# Center_Dash.net
KiCad netlist of a schematic drawn in EAGLE
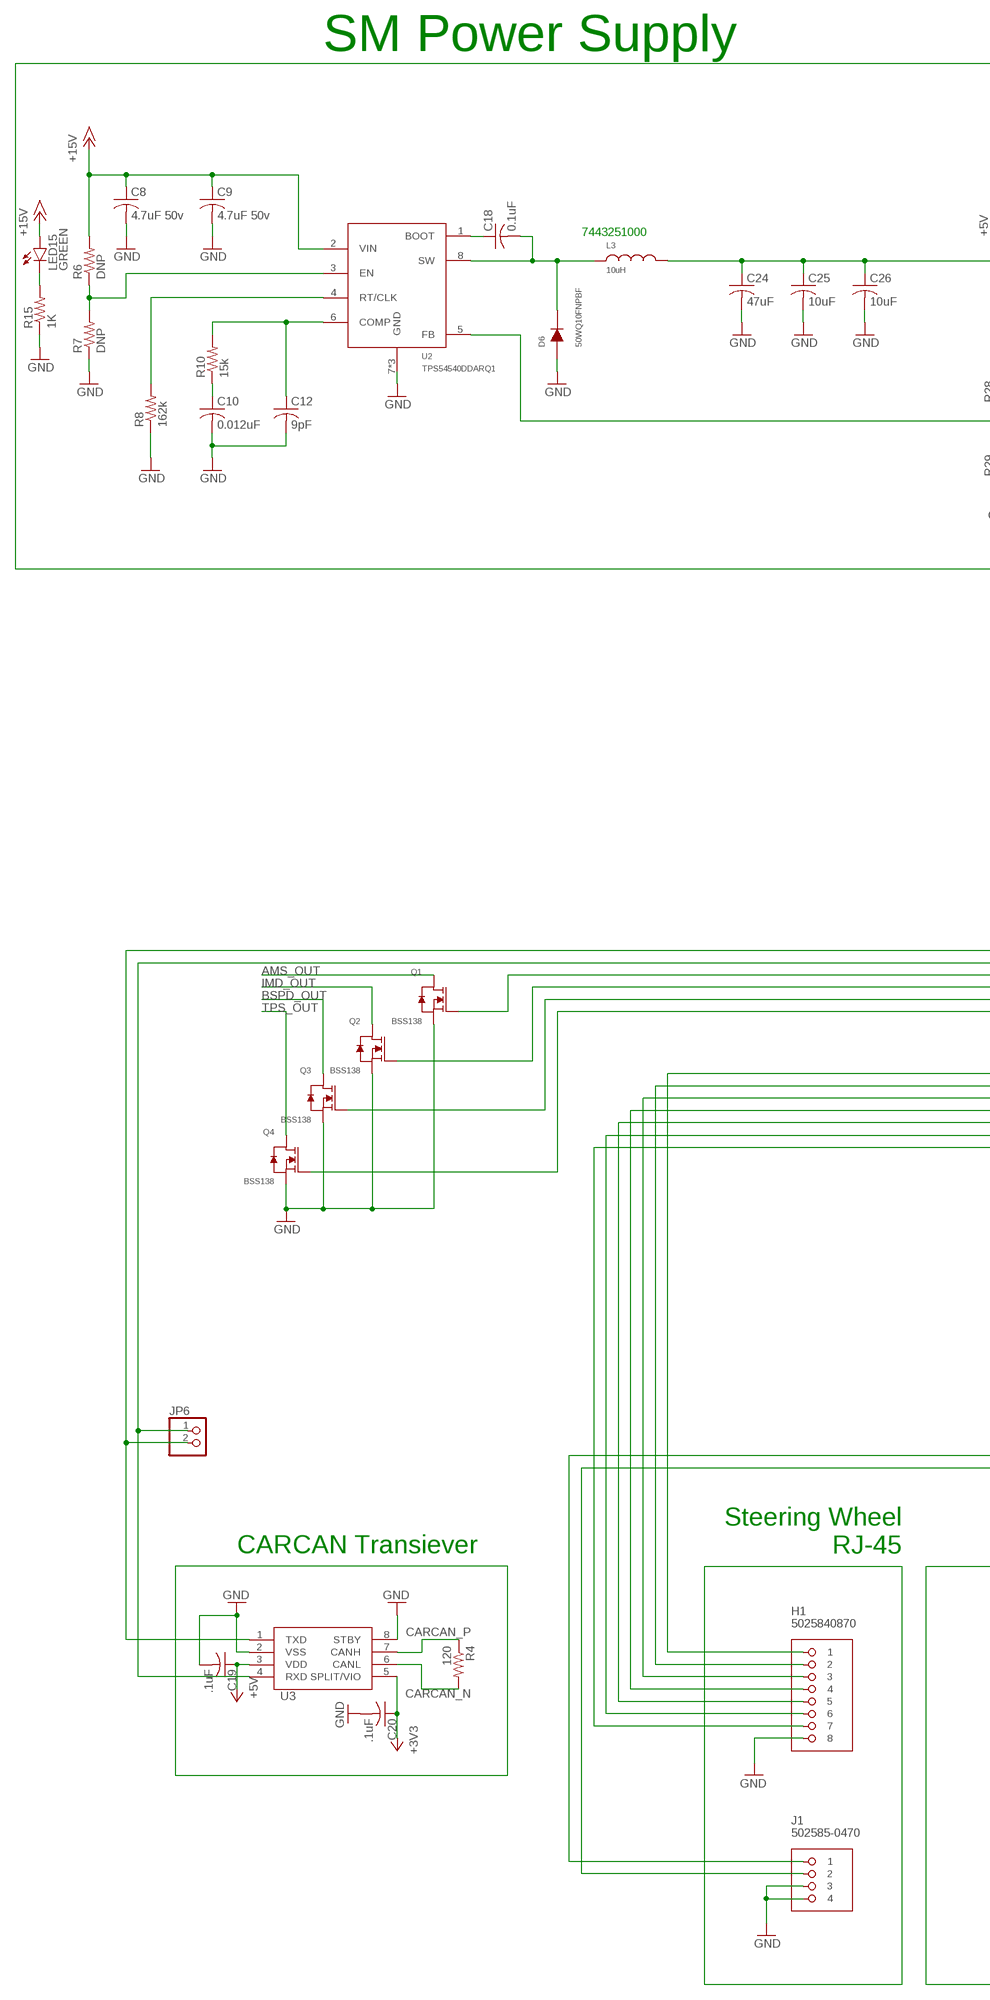
[diagram p0: schematic, sheet 1, part 1 of 2]
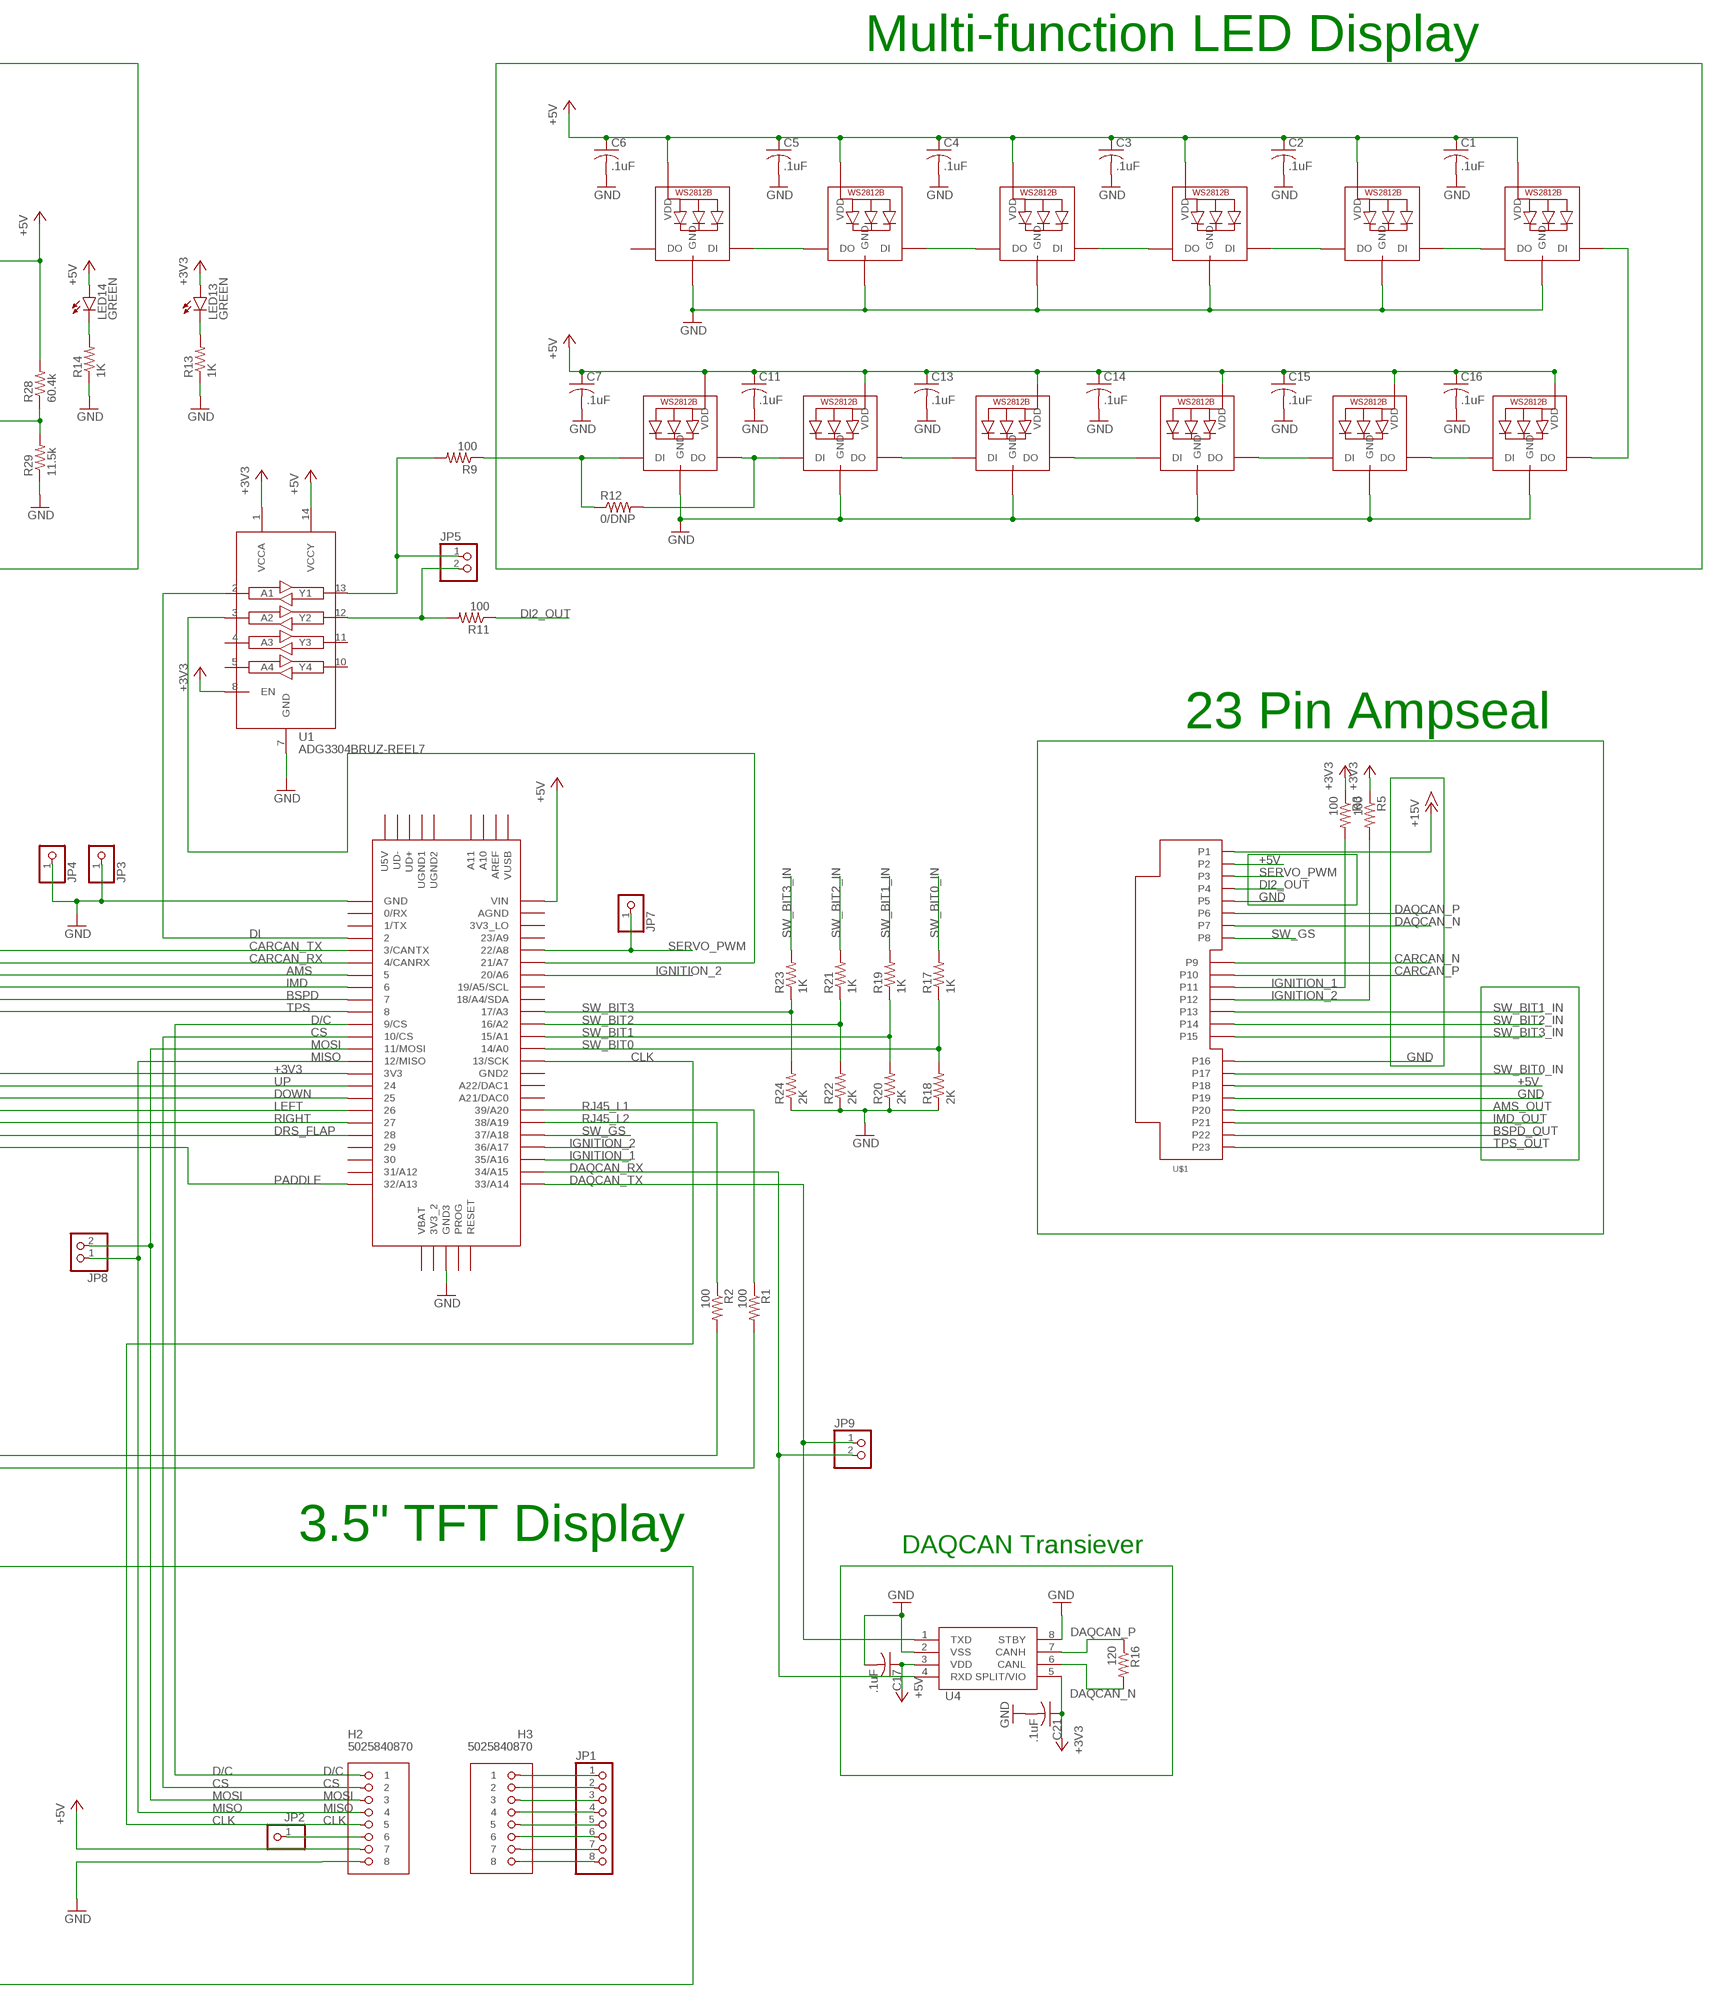
[diagram p1: schematic, sheet 1, part 2 of 2]

(export (version "E")
  (design (tool "Eeschema 10.0.6"))
  (components
    (comp (ref "C1")
      (value ".1uF")
      (footprint "eagle-import:C0603K")
      (fields (field (name "PARTNO") "GRM188R61A106KE69D"))
      (libsource (lib "eagle-import") (part "C-USC0603K"))
    )
    (comp (ref "C2")
      (value ".1uF")
      (footprint "eagle-import:C0603K")
      (fields (field (name "PARTNO") "GRM188R61A106KE69D"))
      (libsource (lib "eagle-import") (part "C-USC0603K"))
    )
    (comp (ref "C3")
      (value ".1uF")
      (footprint "eagle-import:C0603K")
      (fields (field (name "PARTNO") "GRM188R61A106KE69D"))
      (libsource (lib "eagle-import") (part "C-USC0603K"))
    )
    (comp (ref "C4")
      (value ".1uF")
      (footprint "eagle-import:C0603K")
      (fields (field (name "PARTNO") "GRM188R61A106KE69D"))
      (libsource (lib "eagle-import") (part "C-USC0603K"))
    )
    (comp (ref "C5")
      (value ".1uF")
      (footprint "eagle-import:C0603K")
      (fields (field (name "PARTNO") "GRM188R61A106KE69D"))
      (libsource (lib "eagle-import") (part "C-USC0603K"))
    )
    (comp (ref "C6")
      (value ".1uF")
      (footprint "eagle-import:C0603K")
      (fields (field (name "PARTNO") "GRM188R61A106KE69D"))
      (libsource (lib "eagle-import") (part "C-USC0603K"))
    )
    (comp (ref "C7")
      (value ".1uF")
      (footprint "eagle-import:C0603K")
      (fields (field (name "PARTNO") "GRM188R61A106KE69D"))
      (libsource (lib "eagle-import") (part "C-USC0603K"))
    )
    (comp (ref "C8")
      (value "4.7uF 50v")
      (footprint "eagle-import:C1206")
      (fields (field (name "PARTNO") "GRM31CR71H475KA12L"))
      (libsource (lib "eagle-import") (part "C-USC1206"))
    )
    (comp (ref "C9")
      (value "4.7uF 50v")
      (footprint "eagle-import:C1206")
      (fields (field (name "PARTNO") "GRM31CR71H475KA12L"))
      (libsource (lib "eagle-import") (part "C-USC1206"))
    )
    (comp (ref "C10")
      (value "0.012uF")
      (footprint "eagle-import:C0603K")
      (fields (field (name "PARTNO") "GRM188R71H123KA01D"))
      (libsource (lib "eagle-import") (part "C-USC0603K"))
    )
    (comp (ref "C11")
      (value ".1uF")
      (footprint "eagle-import:C0603K")
      (fields (field (name "PARTNO") "GRM188R61A106KE69D"))
      (libsource (lib "eagle-import") (part "C-USC0603K"))
    )
    (comp (ref "C12")
      (value "9pF")
      (footprint "eagle-import:C0603K")
      (fields (field (name "PARTNO") "GRM1885C1H9R0DA01D"))
      (libsource (lib "eagle-import") (part "C-USC0603K"))
    )
    (comp (ref "C13")
      (value ".1uF")
      (footprint "eagle-import:C0603K")
      (fields (field (name "PARTNO") "GRM188R61A106KE69D"))
      (libsource (lib "eagle-import") (part "C-USC0603K"))
    )
    (comp (ref "C14")
      (value ".1uF")
      (footprint "eagle-import:C0603K")
      (fields (field (name "PARTNO") "GRM188R61A106KE69D"))
      (libsource (lib "eagle-import") (part "C-USC0603K"))
    )
    (comp (ref "C15")
      (value ".1uF")
      (footprint "eagle-import:C0603K")
      (fields (field (name "PARTNO") "GRM188R61A106KE69D"))
      (libsource (lib "eagle-import") (part "C-USC0603K"))
    )
    (comp (ref "C16")
      (value ".1uF")
      (footprint "eagle-import:C0603K")
      (fields (field (name "PARTNO") "GRM188R61A106KE69D"))
      (libsource (lib "eagle-import") (part "C-USC0603K"))
    )
    (comp (ref "C17")
      (value ".1uF")
      (footprint "eagle-import:C0805")
      (libsource (lib "eagle-import") (part "C-USC0805"))
    )
    (comp (ref "C18")
      (value "0.1uF")
      (footprint "eagle-import:C0603K")
      (fields (field (name "PARTNO") "GRM188R71E104KA01D"))
      (libsource (lib "eagle-import") (part "C-USC0603K"))
    )
    (comp (ref "C19")
      (value ".1uF")
      (footprint "eagle-import:C0805")
      (libsource (lib "eagle-import") (part "C-USC0805"))
    )
    (comp (ref "C20")
      (value ".1uF")
      (footprint "eagle-import:C0805")
      (libsource (lib "eagle-import") (part "C-USC0805"))
    )
    (comp (ref "C21")
      (value ".1uF")
      (footprint "eagle-import:C0805")
      (libsource (lib "eagle-import") (part "C-USC0805"))
    )
    (comp (ref "C24")
      (value "47uF")
      (footprint "eagle-import:C1206")
      (fields (field (name "PARTNO") "GRM31CR61A476ME15L"))
      (libsource (lib "eagle-import") (part "C-USC1206"))
    )
    (comp (ref "C25")
      (value "10uF")
      (footprint "eagle-import:C0603K")
      (fields (field (name "PARTNO") "GRM188R61A106KE69D"))
      (libsource (lib "eagle-import") (part "C-USC0603K"))
    )
    (comp (ref "C26")
      (value "10uF")
      (footprint "eagle-import:C0603K")
      (fields (field (name "PARTNO") "GRM188R61A106KE69D"))
      (libsource (lib "eagle-import") (part "C-USC0603K"))
    )
    (comp (ref "D6")
      (value "50WQ10FNPBF")
      (footprint "eagle-import:DPAK")
      (fields (field (name "PARTNO") "VS-50WQ10FNPBF"))
      (libsource (lib "eagle-import") (part "VISHAY-50WQ10FNPBF"))
    )
    (comp (ref "H1")
      (value "5025840870")
      (footprint "eagle-import:MOLEX-CLIKMATE-8-VERTICAL-HEADER")
      (libsource (lib "eagle-import") (part "MOLEX_CLICKMATE-8-VERTICAL"))
    )
    (comp (ref "H2")
      (value "5025840870")
      (footprint "eagle-import:MOLEX-CLIKMATE-8-VERTICAL-HEADER")
      (libsource (lib "eagle-import") (part "MOLEX_CLICKMATE-8-VERTICAL"))
    )
    (comp (ref "H3")
      (value "5025840870")
      (footprint "eagle-import:MOLEX-CLIKMATE-8-VERTICAL-HEADER")
      (libsource (lib "eagle-import") (part "MOLEX_CLICKMATE-8-VERTICAL"))
    )
    (comp (ref "J1")
      (value "502585-0470")
      (footprint "eagle-import:MOLEX-CLIKMATE-4-R_A")
      (libsource (lib "eagle-import") (part "MOLEX_CLICKMATE-4-R/A"))
    )
    (comp (ref "JP1")
      (value "PINHD-1X8")
      (footprint "eagle-import:1X08")
      (libsource (lib "eagle-import") (part "PINHD-1X8"))
    )
    (comp (ref "JP2")
      (value "PINHD-1X1")
      (footprint "eagle-import:1X01")
      (libsource (lib "eagle-import") (part "PINHD-1X1"))
    )
    (comp (ref "JP3")
      (value "PINHD-1X1")
      (footprint "eagle-import:1X01")
      (libsource (lib "eagle-import") (part "PINHD-1X1"))
    )
    (comp (ref "JP4")
      (value "PINHD-1X1")
      (footprint "eagle-import:1X01")
      (libsource (lib "eagle-import") (part "PINHD-1X1"))
    )
    (comp (ref "JP5")
      (value "PINHD-1X2")
      (footprint "eagle-import:1X02")
      (libsource (lib "eagle-import") (part "PINHD-1X2"))
    )
    (comp (ref "JP6")
      (value "PINHD-1X2")
      (footprint "eagle-import:1X02")
      (libsource (lib "eagle-import") (part "PINHD-1X2"))
    )
    (comp (ref "JP7")
      (value "PINHD-1X1")
      (footprint "eagle-import:1X01")
      (libsource (lib "eagle-import") (part "PINHD-1X1"))
    )
    (comp (ref "JP8")
      (value "PINHD-1X2")
      (footprint "eagle-import:1X02")
      (libsource (lib "eagle-import") (part "PINHD-1X2"))
    )
    (comp (ref "JP9")
      (value "PINHD-1X2")
      (footprint "eagle-import:1X02")
      (libsource (lib "eagle-import") (part "PINHD-1X2"))
    )
    (comp (ref "L3")
      (value "10uH")
      (footprint "eagle-import:WURTH-744325XXXX")
      (fields (field (name "PARTNO") "7443251000"))
      (libsource (lib "eagle-import") (part "WURTH-744325XXXX"))
    )
    (comp (ref "LED1")
      (value "WS2812B5050")
      (footprint "eagle-import:WS2812B")
      (libsource (lib "eagle-import") (part "WS2812B5050"))
    )
    (comp (ref "LED2")
      (value "WS2812B5050")
      (footprint "eagle-import:WS2812B")
      (libsource (lib "eagle-import") (part "WS2812B5050"))
    )
    (comp (ref "LED3")
      (value "WS2812B5050")
      (footprint "eagle-import:WS2812B")
      (libsource (lib "eagle-import") (part "WS2812B5050"))
    )
    (comp (ref "LED4")
      (value "WS2812B5050")
      (footprint "eagle-import:WS2812B")
      (libsource (lib "eagle-import") (part "WS2812B5050"))
    )
    (comp (ref "LED5")
      (value "WS2812B5050")
      (footprint "eagle-import:WS2812B")
      (libsource (lib "eagle-import") (part "WS2812B5050"))
    )
    (comp (ref "LED6")
      (value "WS2812B5050")
      (footprint "eagle-import:WS2812B")
      (libsource (lib "eagle-import") (part "WS2812B5050"))
    )
    (comp (ref "LED7")
      (value "WS2812B5050")
      (footprint "eagle-import:WS2812B")
      (libsource (lib "eagle-import") (part "WS2812B5050"))
    )
    (comp (ref "LED8")
      (value "WS2812B5050")
      (footprint "eagle-import:WS2812B")
      (libsource (lib "eagle-import") (part "WS2812B5050"))
    )
    (comp (ref "LED9")
      (value "WS2812B5050")
      (footprint "eagle-import:WS2812B")
      (libsource (lib "eagle-import") (part "WS2812B5050"))
    )
    (comp (ref "LED10")
      (value "WS2812B5050")
      (footprint "eagle-import:WS2812B")
      (libsource (lib "eagle-import") (part "WS2812B5050"))
    )
    (comp (ref "LED11")
      (value "WS2812B5050")
      (footprint "eagle-import:WS2812B")
      (libsource (lib "eagle-import") (part "WS2812B5050"))
    )
    (comp (ref "LED12")
      (value "WS2812B5050")
      (footprint "eagle-import:WS2812B")
      (libsource (lib "eagle-import") (part "WS2812B5050"))
    )
    (comp (ref "LED13")
      (value "GREEN")
      (footprint "eagle-import:CHIP-LED0805")
      (fields (field (name "PARTNO") "598-8170-107F"))
      (libsource (lib "eagle-import") (part "LEDCHIP-LED0805"))
    )
    (comp (ref "LED14")
      (value "GREEN")
      (footprint "eagle-import:CHIP-LED0805")
      (fields (field (name "PARTNO") "598-8170-107F"))
      (libsource (lib "eagle-import") (part "LEDCHIP-LED0805"))
    )
    (comp (ref "LED15")
      (value "GREEN")
      (footprint "eagle-import:CHIP-LED0805")
      (fields (field (name "PARTNO") "598-8170-107F"))
      (libsource (lib "eagle-import") (part "LEDCHIP-LED0805"))
    )
    (comp (ref "Q1")
      (value "BSS138")
      (footprint "eagle-import:BSS138")
      (libsource (lib "eagle-import") (part "BSS138"))
    )
    (comp (ref "Q2")
      (value "BSS138")
      (footprint "eagle-import:BSS138")
      (libsource (lib "eagle-import") (part "BSS138"))
    )
    (comp (ref "Q3")
      (value "BSS138")
      (footprint "eagle-import:BSS138")
      (libsource (lib "eagle-import") (part "BSS138"))
    )
    (comp (ref "Q4")
      (value "BSS138")
      (footprint "eagle-import:BSS138")
      (libsource (lib "eagle-import") (part "BSS138"))
    )
    (comp (ref "R1")
      (value "100")
      (footprint "eagle-import:R0805")
      (libsource (lib "eagle-import") (part "rcl_R-US_R0805"))
    )
    (comp (ref "R2")
      (value "100")
      (footprint "eagle-import:R0805")
      (libsource (lib "eagle-import") (part "rcl_R-US_R0805"))
    )
    (comp (ref "R3")
      (value "100")
      (footprint "eagle-import:R0805")
      (libsource (lib "eagle-import") (part "rcl_R-US_R0805"))
    )
    (comp (ref "R4")
      (value "120")
      (footprint "eagle-import:R0805")
      (libsource (lib "eagle-import") (part "rcl_R-US_R0805"))
    )
    (comp (ref "R5")
      (value "100")
      (footprint "eagle-import:R0805")
      (libsource (lib "eagle-import") (part "rcl_R-US_R0805"))
    )
    (comp (ref "R6")
      (value "DNP")
      (footprint "eagle-import:R0603")
      (libsource (lib "eagle-import") (part "rcl_R-US_R0603"))
    )
    (comp (ref "R7")
      (value "DNP")
      (footprint "eagle-import:R0603")
      (libsource (lib "eagle-import") (part "rcl_R-US_R0603"))
    )
    (comp (ref "R8")
      (value "162k")
      (footprint "eagle-import:R0603")
      (fields (field (name "PARTNO") "ERJ-3EKF1623V"))
      (libsource (lib "eagle-import") (part "rcl_R-US_R0603"))
    )
    (comp (ref "R9")
      (value "100")
      (footprint "eagle-import:R0805")
      (libsource (lib "eagle-import") (part "rcl_R-US_R0805"))
    )
    (comp (ref "R10")
      (value "15k")
      (footprint "eagle-import:R0603")
      (fields (field (name "PARTNO") "ERJ-3EKF1502V"))
      (libsource (lib "eagle-import") (part "rcl_R-US_R0603"))
    )
    (comp (ref "R11")
      (value "100")
      (footprint "eagle-import:R0805")
      (libsource (lib "eagle-import") (part "rcl_R-US_R0805"))
    )
    (comp (ref "R12")
      (value "0/DNP")
      (footprint "eagle-import:R0805")
      (libsource (lib "eagle-import") (part "rcl_R-US_R0805"))
    )
    (comp (ref "R13")
      (value "1K")
      (footprint "eagle-import:R0805")
      (fields (field (name "PARTNO") "ERJ-6ENF1001V"))
      (libsource (lib "eagle-import") (part "R-US_R0805"))
    )
    (comp (ref "R14")
      (value "1K")
      (footprint "eagle-import:R0805")
      (fields (field (name "PARTNO") "ERJ-6ENF1001V"))
      (libsource (lib "eagle-import") (part "R-US_R0805"))
    )
    (comp (ref "R15")
      (value "1K")
      (footprint "eagle-import:R0805")
      (fields (field (name "PARTNO") "ERJ-6ENF1001V"))
      (libsource (lib "eagle-import") (part "R-US_R0805"))
    )
    (comp (ref "R16")
      (value "120")
      (footprint "eagle-import:R0805")
      (libsource (lib "eagle-import") (part "rcl_R-US_R0805"))
    )
    (comp (ref "R17")
      (value "1K")
      (footprint "eagle-import:R0805")
      (fields (field (name "PARTNO") "ERJ-6ENF1001V"))
      (libsource (lib "eagle-import") (part "R-US_R0805"))
    )
    (comp (ref "R18")
      (value "2K")
      (footprint "eagle-import:R0805")
      (fields (field (name "PARTNO") "ERJ-6ENF1001V"))
      (libsource (lib "eagle-import") (part "R-US_R0805"))
    )
    (comp (ref "R19")
      (value "1K")
      (footprint "eagle-import:R0805")
      (fields (field (name "PARTNO") "ERJ-6ENF1001V"))
      (libsource (lib "eagle-import") (part "R-US_R0805"))
    )
    (comp (ref "R20")
      (value "2K")
      (footprint "eagle-import:R0805")
      (fields (field (name "PARTNO") "ERJ-6ENF1001V"))
      (libsource (lib "eagle-import") (part "R-US_R0805"))
    )
    (comp (ref "R21")
      (value "1K")
      (footprint "eagle-import:R0805")
      (fields (field (name "PARTNO") "ERJ-6ENF1001V"))
      (libsource (lib "eagle-import") (part "R-US_R0805"))
    )
    (comp (ref "R22")
      (value "2K")
      (footprint "eagle-import:R0805")
      (fields (field (name "PARTNO") "ERJ-6ENF1001V"))
      (libsource (lib "eagle-import") (part "R-US_R0805"))
    )
    (comp (ref "R23")
      (value "1K")
      (footprint "eagle-import:R0805")
      (fields (field (name "PARTNO") "ERJ-6ENF1001V"))
      (libsource (lib "eagle-import") (part "R-US_R0805"))
    )
    (comp (ref "R24")
      (value "2K")
      (footprint "eagle-import:R0805")
      (fields (field (name "PARTNO") "ERJ-6ENF1001V"))
      (libsource (lib "eagle-import") (part "R-US_R0805"))
    )
    (comp (ref "R28")
      (value "60.4k")
      (footprint "eagle-import:R0603")
      (fields (field (name "PARTNO") "ERJ-3EKF6042V"))
      (libsource (lib "eagle-import") (part "rcl_R-US_R0603"))
    )
    (comp (ref "R29")
      (value "11.5k")
      (footprint "eagle-import:R0603")
      (fields (field (name "PARTNO") "ERJ-3EKF1152V"))
      (libsource (lib "eagle-import") (part "rcl_R-US_R0603"))
    )
    (comp (ref "U$1")
      (value "TE-776200-1")
      (footprint "eagle-import:TE-776200-1")
      (libsource (lib "eagle-import") (part "TE-776200-1"))
    )
    (comp (ref "U$2")
      (value "TEENSY_3.5/3.6")
      (footprint "eagle-import:TEENSY_3.5_3.6")
      (libsource (lib "eagle-import") (part "TEENSY_3.5/3.6"))
    )
    (comp (ref "U1")
      (value "ADG3304BRUZ-REEL7")
      (footprint "eagle-import:ADG3304")
      (libsource (lib "eagle-import") (part "ADG3304"))
    )
    (comp (ref "U2")
      (value "TPS54540DDARQ1")
      (footprint "eagle-import:TPS54540")
      (fields (field (name "PARTNO") "TPS54540DDAR"))
      (libsource (lib "eagle-import") (part "TPS54540"))
    )
    (comp (ref "U3")
      (value "MCP256X-SOIC")
      (footprint "eagle-import:SOIC8-N_MC")
      (libsource (lib "eagle-import") (part "MCP256X-SOIC"))
    )
    (comp (ref "U4")
      (value "MCP256X-SOIC")
      (footprint "eagle-import:SOIC8-N_MC")
      (libsource (lib "eagle-import") (part "MCP256X-SOIC"))
    )
  )
  (nets
    (net (code "1") (name "+3V3") (class "Default")
      (node (ref "C20") (pin "1") (pinfunction "1_1") (pintype "passive"))
      (node (ref "C21") (pin "1") (pinfunction "1_1") (pintype "passive"))
      (node (ref "H1") (pin "1") (pinfunction "1_1") (pintype "bidirectional"))
      (node (ref "LED13") (pin "A") (pinfunction "A_A") (pintype "passive"))
      (node (ref "R3") (pin "1") (pinfunction "1_1") (pintype "passive"))
      (node (ref "R5") (pin "1") (pinfunction "1_1") (pintype "passive"))
      (node (ref "U$2") (pin "3V3") (pinfunction "3V3_3V3") (pintype "bidirectional"))
      (node (ref "U1") (pin "1") (pinfunction "VCCA_1") (pintype "bidirectional"))
      (node (ref "U1") (pin "8") (pinfunction "EN_8") (pintype "bidirectional"))
      (node (ref "U3") (pin "5") (pinfunction "SPLIT/VIO_5") (pintype "bidirectional"))
      (node (ref "U4") (pin "5") (pinfunction "SPLIT/VIO_5") (pintype "bidirectional"))
    )
    (net (code "2") (name "+5V") (class "Default")
      (node (ref "C1") (pin "1") (pinfunction "1_1") (pintype "passive"))
      (node (ref "C11") (pin "1") (pinfunction "1_1") (pintype "passive"))
      (node (ref "C13") (pin "1") (pinfunction "1_1") (pintype "passive"))
      (node (ref "C14") (pin "1") (pinfunction "1_1") (pintype "passive"))
      (node (ref "C15") (pin "1") (pinfunction "1_1") (pintype "passive"))
      (node (ref "C16") (pin "1") (pinfunction "1_1") (pintype "passive"))
      (node (ref "C17") (pin "1") (pinfunction "1_1") (pintype "passive"))
      (node (ref "C19") (pin "1") (pinfunction "1_1") (pintype "passive"))
      (node (ref "C2") (pin "1") (pinfunction "1_1") (pintype "passive"))
      (node (ref "C24") (pin "1") (pinfunction "1_1") (pintype "passive"))
      (node (ref "C25") (pin "1") (pinfunction "1_1") (pintype "passive"))
      (node (ref "C26") (pin "1") (pinfunction "1_1") (pintype "passive"))
      (node (ref "C3") (pin "1") (pinfunction "1_1") (pintype "passive"))
      (node (ref "C4") (pin "1") (pinfunction "1_1") (pintype "passive"))
      (node (ref "C5") (pin "1") (pinfunction "1_1") (pintype "passive"))
      (node (ref "C6") (pin "1") (pinfunction "1_1") (pintype "passive"))
      (node (ref "C7") (pin "1") (pinfunction "1_1") (pintype "passive"))
      (node (ref "H2") (pin "7") (pinfunction "7_7") (pintype "bidirectional"))
      (node (ref "L3") (pin "P$2") (pinfunction "P$2_P$2") (pintype "bidirectional"))
      (node (ref "LED1") (pin "1-VDD") (pinfunction "VDD_1-VDD") (pintype "power_in"))
      (node (ref "LED10") (pin "1-VDD") (pinfunction "VDD_1-VDD") (pintype "power_in"))
      (node (ref "LED11") (pin "1-VDD") (pinfunction "VDD_1-VDD") (pintype "power_in"))
      (node (ref "LED12") (pin "1-VDD") (pinfunction "VDD_1-VDD") (pintype "power_in"))
      (node (ref "LED14") (pin "A") (pinfunction "A_A") (pintype "passive"))
      (node (ref "LED2") (pin "1-VDD") (pinfunction "VDD_1-VDD") (pintype "power_in"))
      (node (ref "LED3") (pin "1-VDD") (pinfunction "VDD_1-VDD") (pintype "power_in"))
      (node (ref "LED4") (pin "1-VDD") (pinfunction "VDD_1-VDD") (pintype "power_in"))
      (node (ref "LED5") (pin "1-VDD") (pinfunction "VDD_1-VDD") (pintype "power_in"))
      (node (ref "LED6") (pin "1-VDD") (pinfunction "VDD_1-VDD") (pintype "power_in"))
      (node (ref "LED7") (pin "1-VDD") (pinfunction "VDD_1-VDD") (pintype "power_in"))
      (node (ref "LED8") (pin "1-VDD") (pinfunction "VDD_1-VDD") (pintype "power_in"))
      (node (ref "LED9") (pin "1-VDD") (pinfunction "VDD_1-VDD") (pintype "power_in"))
      (node (ref "R28") (pin "2") (pinfunction "2_2") (pintype "passive"))
      (node (ref "U$1") (pin "P$18") (pinfunction "P18_P$18") (pintype "bidirectional"))
      (node (ref "U$1") (pin "P$2") (pinfunction "P2_P$2") (pintype "bidirectional"))
      (node (ref "U$2") (pin "VIN") (pinfunction "VIN_VIN") (pintype "bidirectional"))
      (node (ref "U1") (pin "14") (pinfunction "VCCY_14") (pintype "bidirectional"))
      (node (ref "U3") (pin "3") (pinfunction "VDD_3") (pintype "power_in"))
      (node (ref "U4") (pin "3") (pinfunction "VDD_3") (pintype "power_in"))
    )
    (net (code "3") (name "+15V") (class "Default")
      (node (ref "C8") (pin "1") (pinfunction "1_1") (pintype "passive"))
      (node (ref "C9") (pin "1") (pinfunction "1_1") (pintype "passive"))
      (node (ref "LED15") (pin "A") (pinfunction "A_A") (pintype "passive"))
      (node (ref "R6") (pin "2") (pinfunction "2_2") (pintype "passive"))
      (node (ref "U$1") (pin "P$1") (pinfunction "P1_P$1") (pintype "bidirectional"))
      (node (ref "U2") (pin "2") (pinfunction "VIN_2") (pintype "bidirectional"))
    )
    (net (code "4") (name "/AMS") (class "Default")
      (node (ref "Q1") (pin "G") (pinfunction "G_G") (pintype "bidirectional"))
      (node (ref "U$2") (pin "5") (pinfunction "5_5") (pintype "bidirectional"))
    )
    (net (code "5") (name "/AMS_OUT") (class "Default")
      (node (ref "Q1") (pin "D") (pinfunction "D_D") (pintype "bidirectional"))
      (node (ref "U$1") (pin "P$20") (pinfunction "P20_P$20") (pintype "bidirectional"))
    )
    (net (code "6") (name "/BSPD") (class "Default")
      (node (ref "Q3") (pin "G") (pinfunction "G_G") (pintype "bidirectional"))
      (node (ref "U$2") (pin "7") (pinfunction "7_7") (pintype "bidirectional"))
    )
    (net (code "7") (name "/BSPD_OUT") (class "Default")
      (node (ref "Q3") (pin "D") (pinfunction "D_D") (pintype "bidirectional"))
      (node (ref "U$1") (pin "P$22") (pinfunction "P22_P$22") (pintype "bidirectional"))
    )
    (net (code "8") (name "/CARCAN_N") (class "Default")
      (node (ref "R4") (pin "2") (pinfunction "2_2") (pintype "passive"))
      (node (ref "U$1") (pin "P$9") (pinfunction "P9_P$9") (pintype "bidirectional"))
      (node (ref "U3") (pin "6") (pinfunction "CANL_6") (pintype "bidirectional"))
    )
    (net (code "9") (name "/CARCAN_P") (class "Default")
      (node (ref "R4") (pin "1") (pinfunction "1_1") (pintype "passive"))
      (node (ref "U$1") (pin "P$10") (pinfunction "P10_P$10") (pintype "bidirectional"))
      (node (ref "U3") (pin "7") (pinfunction "CANH_7") (pintype "bidirectional"))
    )
    (net (code "10") (name "/CARCAN_RX") (class "Default")
      (node (ref "JP6") (pin "1") (pinfunction "1_1") (pintype "passive"))
      (node (ref "U$2") (pin "4/CANRX") (pinfunction "4/CANRX_4/CANRX") (pintype "bidirectional"))
      (node (ref "U3") (pin "4") (pinfunction "RXD_4") (pintype "bidirectional"))
    )
    (net (code "11") (name "/CARCAN_TX") (class "Default")
      (node (ref "JP6") (pin "2") (pinfunction "2_2") (pintype "passive"))
      (node (ref "U$2") (pin "3/CANTX") (pinfunction "3/CANTX_3/CANTX") (pintype "bidirectional"))
      (node (ref "U3") (pin "1") (pinfunction "TXD_1") (pintype "bidirectional"))
    )
    (net (code "12") (name "/CLK") (class "Default")
      (node (ref "H2") (pin "5") (pinfunction "5_5") (pintype "bidirectional"))
      (node (ref "U$2") (pin "13/SCK") (pinfunction "13/SCK_13/SCK") (pintype "bidirectional"))
    )
    (net (code "13") (name "/CS") (class "Default")
      (node (ref "H2") (pin "2") (pinfunction "2_2") (pintype "bidirectional"))
      (node (ref "U$2") (pin "10/CS") (pinfunction "10/CS_10/CS") (pintype "bidirectional"))
    )
    (net (code "14") (name "/DAQCAN_N") (class "Default")
      (node (ref "R16") (pin "2") (pinfunction "2_2") (pintype "passive"))
      (node (ref "U$1") (pin "P$7") (pinfunction "P7_P$7") (pintype "bidirectional"))
      (node (ref "U4") (pin "6") (pinfunction "CANL_6") (pintype "bidirectional"))
    )
    (net (code "15") (name "/DAQCAN_P") (class "Default")
      (node (ref "R16") (pin "1") (pinfunction "1_1") (pintype "passive"))
      (node (ref "U$1") (pin "P$6") (pinfunction "P6_P$6") (pintype "bidirectional"))
      (node (ref "U4") (pin "7") (pinfunction "CANH_7") (pintype "bidirectional"))
    )
    (net (code "16") (name "/DAQCAN_RX") (class "Default")
      (node (ref "JP9") (pin "2") (pinfunction "2_2") (pintype "passive"))
      (node (ref "U$2") (pin "34/A15") (pinfunction "34/A15_34/A15") (pintype "bidirectional"))
      (node (ref "U4") (pin "4") (pinfunction "RXD_4") (pintype "bidirectional"))
    )
    (net (code "17") (name "/DAQCAN_TX") (class "Default")
      (node (ref "JP9") (pin "1") (pinfunction "1_1") (pintype "passive"))
      (node (ref "U$2") (pin "33/A14") (pinfunction "33/A14_33/A14") (pintype "bidirectional"))
      (node (ref "U4") (pin "1") (pinfunction "TXD_1") (pintype "bidirectional"))
    )
    (net (code "18") (name "/DI") (class "Default")
      (node (ref "U$2") (pin "2") (pinfunction "2_2") (pintype "bidirectional"))
      (node (ref "U1") (pin "2") (pinfunction "A1_2") (pintype "bidirectional"))
    )
    (net (code "19") (name "/DI2_OUT") (class "Default")
      (node (ref "R11") (pin "1") (pinfunction "1_1") (pintype "passive"))
      (node (ref "U$1") (pin "P$4") (pinfunction "P4_P$4") (pintype "bidirectional"))
    )
    (net (code "20") (name "/DOWN") (class "Default")
      (node (ref "H1") (pin "3") (pinfunction "3_3") (pintype "bidirectional"))
      (node (ref "U$2") (pin "25") (pinfunction "25_25") (pintype "bidirectional"))
    )
    (net (code "21") (name "/DRS_FLAP") (class "Default")
      (node (ref "H1") (pin "6") (pinfunction "6_6") (pintype "bidirectional"))
      (node (ref "U$2") (pin "28") (pinfunction "28_28") (pintype "bidirectional"))
    )
    (net (code "22") (name "/D{slash}C") (class "Default")
      (node (ref "H2") (pin "1") (pinfunction "1_1") (pintype "bidirectional"))
      (node (ref "U$2") (pin "9/CS") (pinfunction "9/CS_9/CS") (pintype "bidirectional"))
    )
    (net (code "23") (name "/IGNITION_1") (class "Default")
      (node (ref "R3") (pin "2") (pinfunction "2_2") (pintype "passive"))
      (node (ref "U$1") (pin "P$11") (pinfunction "P11_P$11") (pintype "bidirectional"))
      (node (ref "U$2") (pin "35/A16") (pinfunction "35/A16_35/A16") (pintype "bidirectional"))
    )
    (net (code "24") (name "/IGNITION_2") (class "Default")
      (node (ref "R5") (pin "2") (pinfunction "2_2") (pintype "passive"))
      (node (ref "U$1") (pin "P$12") (pinfunction "P12_P$12") (pintype "bidirectional"))
      (node (ref "U$2") (pin "20/A6") (pinfunction "20/A6_20/A6") (pintype "bidirectional"))
      (node (ref "U$2") (pin "36/A17") (pinfunction "36/A17_36/A17") (pintype "bidirectional"))
    )
    (net (code "25") (name "/IMD") (class "Default")
      (node (ref "Q2") (pin "G") (pinfunction "G_G") (pintype "bidirectional"))
      (node (ref "U$2") (pin "6") (pinfunction "6_6") (pintype "bidirectional"))
    )
    (net (code "26") (name "/IMD_OUT") (class "Default")
      (node (ref "Q2") (pin "D") (pinfunction "D_D") (pintype "bidirectional"))
      (node (ref "U$1") (pin "P$21") (pinfunction "P21_P$21") (pintype "bidirectional"))
    )
    (net (code "27") (name "/LEFT") (class "Default")
      (node (ref "H1") (pin "4") (pinfunction "4_4") (pintype "bidirectional"))
      (node (ref "U$2") (pin "26") (pinfunction "26_26") (pintype "bidirectional"))
    )
    (net (code "28") (name "/MISO") (class "Default")
      (node (ref "H2") (pin "4") (pinfunction "4_4") (pintype "bidirectional"))
      (node (ref "JP8") (pin "1") (pinfunction "1_1") (pintype "passive"))
      (node (ref "U$2") (pin "12/MISO") (pinfunction "12/MISO_12/MISO") (pintype "bidirectional"))
    )
    (net (code "29") (name "/MOSI") (class "Default")
      (node (ref "H2") (pin "3") (pinfunction "3_3") (pintype "bidirectional"))
      (node (ref "JP8") (pin "2") (pinfunction "2_2") (pintype "passive"))
      (node (ref "U$2") (pin "11/MOSI") (pinfunction "11/MOSI_11/MOSI") (pintype "bidirectional"))
    )
    (net (code "30") (name "/PADDLE") (class "Default")
      (node (ref "H1") (pin "7") (pinfunction "7_7") (pintype "bidirectional"))
      (node (ref "U$2") (pin "32/A13") (pinfunction "32/A13_32/A13") (pintype "bidirectional"))
    )
    (net (code "31") (name "/RIGHT") (class "Default")
      (node (ref "H1") (pin "5") (pinfunction "5_5") (pintype "bidirectional"))
      (node (ref "U$2") (pin "27") (pinfunction "27_27") (pintype "bidirectional"))
    )
    (net (code "32") (name "/RJ45_L1") (class "Default")
      (node (ref "R1") (pin "1") (pinfunction "1_1") (pintype "passive"))
      (node (ref "U$2") (pin "39/A20") (pinfunction "39/A20_39/A20") (pintype "bidirectional"))
    )
    (net (code "33") (name "/RJ45_L2") (class "Default")
      (node (ref "R2") (pin "1") (pinfunction "1_1") (pintype "passive"))
      (node (ref "U$2") (pin "38/A19") (pinfunction "38/A19_38/A19") (pintype "bidirectional"))
    )
    (net (code "34") (name "/SERVO_PWM") (class "Default")
      (node (ref "JP7") (pin "1") (pinfunction "1_1") (pintype "passive"))
      (node (ref "U$1") (pin "P$3") (pinfunction "P3_P$3") (pintype "bidirectional"))
      (node (ref "U$2") (pin "22/A8") (pinfunction "22/A8_22/A8") (pintype "bidirectional"))
    )
    (net (code "35") (name "/SW_BIT0") (class "Default")
      (node (ref "R17") (pin "1") (pinfunction "1_1") (pintype "passive"))
      (node (ref "R18") (pin "2") (pinfunction "2_2") (pintype "passive"))
      (node (ref "U$2") (pin "14/A0") (pinfunction "14/A0_14/A0") (pintype "bidirectional"))
    )
    (net (code "36") (name "/SW_BIT0_IN") (class "Default")
      (node (ref "R17") (pin "2") (pinfunction "2_2") (pintype "passive"))
      (node (ref "U$1") (pin "P$17") (pinfunction "P17_P$17") (pintype "bidirectional"))
    )
    (net (code "37") (name "/SW_BIT1") (class "Default")
      (node (ref "R19") (pin "1") (pinfunction "1_1") (pintype "passive"))
      (node (ref "R20") (pin "2") (pinfunction "2_2") (pintype "passive"))
      (node (ref "U$2") (pin "15/A1") (pinfunction "15/A1_15/A1") (pintype "bidirectional"))
    )
    (net (code "38") (name "/SW_BIT1_IN") (class "Default")
      (node (ref "R19") (pin "2") (pinfunction "2_2") (pintype "passive"))
      (node (ref "U$1") (pin "P$13") (pinfunction "P13_P$13") (pintype "bidirectional"))
    )
    (net (code "39") (name "/SW_BIT2") (class "Default")
      (node (ref "R21") (pin "1") (pinfunction "1_1") (pintype "passive"))
      (node (ref "R22") (pin "2") (pinfunction "2_2") (pintype "passive"))
      (node (ref "U$2") (pin "16/A2") (pinfunction "16/A2_16/A2") (pintype "bidirectional"))
    )
    (net (code "40") (name "/SW_BIT2_IN") (class "Default")
      (node (ref "R21") (pin "2") (pinfunction "2_2") (pintype "passive"))
      (node (ref "U$1") (pin "P$14") (pinfunction "P14_P$14") (pintype "bidirectional"))
    )
    (net (code "41") (name "/SW_BIT3") (class "Default")
      (node (ref "R23") (pin "1") (pinfunction "1_1") (pintype "passive"))
      (node (ref "R24") (pin "2") (pinfunction "2_2") (pintype "passive"))
      (node (ref "U$2") (pin "17/A3") (pinfunction "17/A3_17/A3") (pintype "bidirectional"))
    )
    (net (code "42") (name "/SW_BIT3_IN") (class "Default")
      (node (ref "R23") (pin "2") (pinfunction "2_2") (pintype "passive"))
      (node (ref "U$1") (pin "P$15") (pinfunction "P15_P$15") (pintype "bidirectional"))
    )
    (net (code "43") (name "/SW_GS") (class "Default")
      (node (ref "U$1") (pin "P$8") (pinfunction "P8_P$8") (pintype "bidirectional"))
      (node (ref "U$2") (pin "37/A18") (pinfunction "37/A18_37/A18") (pintype "bidirectional"))
    )
    (net (code "44") (name "/TPS") (class "Default")
      (node (ref "Q4") (pin "G") (pinfunction "G_G") (pintype "bidirectional"))
      (node (ref "U$2") (pin "8") (pinfunction "8_8") (pintype "bidirectional"))
    )
    (net (code "45") (name "/TPS_OUT") (class "Default")
      (node (ref "Q4") (pin "D") (pinfunction "D_D") (pintype "bidirectional"))
      (node (ref "U$1") (pin "P$23") (pinfunction "P23_P$23") (pintype "bidirectional"))
    )
    (net (code "46") (name "/UP") (class "Default")
      (node (ref "H1") (pin "2") (pinfunction "2_2") (pintype "bidirectional"))
      (node (ref "U$2") (pin "24") (pinfunction "24_24") (pintype "bidirectional"))
    )
    (net (code "47") (name "GND") (class "Default")
      (node (ref "C1") (pin "2") (pinfunction "2_2") (pintype "passive"))
      (node (ref "C10") (pin "2") (pinfunction "2_2") (pintype "passive"))
      (node (ref "C11") (pin "2") (pinfunction "2_2") (pintype "passive"))
      (node (ref "C12") (pin "2") (pinfunction "2_2") (pintype "passive"))
      (node (ref "C13") (pin "2") (pinfunction "2_2") (pintype "passive"))
      (node (ref "C14") (pin "2") (pinfunction "2_2") (pintype "passive"))
      (node (ref "C15") (pin "2") (pinfunction "2_2") (pintype "passive"))
      (node (ref "C16") (pin "2") (pinfunction "2_2") (pintype "passive"))
      (node (ref "C17") (pin "2") (pinfunction "2_2") (pintype "passive"))
      (node (ref "C19") (pin "2") (pinfunction "2_2") (pintype "passive"))
      (node (ref "C2") (pin "2") (pinfunction "2_2") (pintype "passive"))
      (node (ref "C20") (pin "2") (pinfunction "2_2") (pintype "passive"))
      (node (ref "C21") (pin "2") (pinfunction "2_2") (pintype "passive"))
      (node (ref "C24") (pin "2") (pinfunction "2_2") (pintype "passive"))
      (node (ref "C25") (pin "2") (pinfunction "2_2") (pintype "passive"))
      (node (ref "C26") (pin "2") (pinfunction "2_2") (pintype "passive"))
      (node (ref "C3") (pin "2") (pinfunction "2_2") (pintype "passive"))
      (node (ref "C4") (pin "2") (pinfunction "2_2") (pintype "passive"))
      (node (ref "C5") (pin "2") (pinfunction "2_2") (pintype "passive"))
      (node (ref "C6") (pin "2") (pinfunction "2_2") (pintype "passive"))
      (node (ref "C7") (pin "2") (pinfunction "2_2") (pintype "passive"))
      (node (ref "C8") (pin "2") (pinfunction "2_2") (pintype "passive"))
      (node (ref "C9") (pin "2") (pinfunction "2_2") (pintype "passive"))
      (node (ref "D6") (pin "1") (pinfunction "ANODE_1") (pintype "bidirectional"))
      (node (ref "D6") (pin "3") (pinfunction "ANODE_3") (pintype "bidirectional"))
      (node (ref "H1") (pin "8") (pinfunction "8_8") (pintype "bidirectional"))
      (node (ref "H2") (pin "8") (pinfunction "8_8") (pintype "bidirectional"))
      (node (ref "J1") (pin "3") (pinfunction "3_3") (pintype "bidirectional"))
      (node (ref "J1") (pin "4") (pinfunction "4_4") (pintype "bidirectional"))
      (node (ref "JP3") (pin "1") (pinfunction "1_1") (pintype "passive"))
      (node (ref "JP4") (pin "1") (pinfunction "1_1") (pintype "passive"))
      (node (ref "LED1") (pin "3-GND") (pinfunction "GND_3-GND") (pintype "power_in"))
      (node (ref "LED10") (pin "3-GND") (pinfunction "GND_3-GND") (pintype "power_in"))
      (node (ref "LED11") (pin "3-GND") (pinfunction "GND_3-GND") (pintype "power_in"))
      (node (ref "LED12") (pin "3-GND") (pinfunction "GND_3-GND") (pintype "power_in"))
      (node (ref "LED2") (pin "3-GND") (pinfunction "GND_3-GND") (pintype "power_in"))
      (node (ref "LED3") (pin "3-GND") (pinfunction "GND_3-GND") (pintype "power_in"))
      (node (ref "LED4") (pin "3-GND") (pinfunction "GND_3-GND") (pintype "power_in"))
      (node (ref "LED5") (pin "3-GND") (pinfunction "GND_3-GND") (pintype "power_in"))
      (node (ref "LED6") (pin "3-GND") (pinfunction "GND_3-GND") (pintype "power_in"))
      (node (ref "LED7") (pin "3-GND") (pinfunction "GND_3-GND") (pintype "power_in"))
      (node (ref "LED8") (pin "3-GND") (pinfunction "GND_3-GND") (pintype "power_in"))
      (node (ref "LED9") (pin "3-GND") (pinfunction "GND_3-GND") (pintype "power_in"))
      (node (ref "Q1") (pin "S") (pinfunction "S_S") (pintype "bidirectional"))
      (node (ref "Q2") (pin "S") (pinfunction "S_S") (pintype "bidirectional"))
      (node (ref "Q3") (pin "S") (pinfunction "S_S") (pintype "bidirectional"))
      (node (ref "Q4") (pin "S") (pinfunction "S_S") (pintype "bidirectional"))
      (node (ref "R13") (pin "1") (pinfunction "1_1") (pintype "passive"))
      (node (ref "R14") (pin "1") (pinfunction "1_1") (pintype "passive"))
      (node (ref "R15") (pin "1") (pinfunction "1_1") (pintype "passive"))
      (node (ref "R18") (pin "1") (pinfunction "1_1") (pintype "passive"))
      (node (ref "R20") (pin "1") (pinfunction "1_1") (pintype "passive"))
      (node (ref "R22") (pin "1") (pinfunction "1_1") (pintype "passive"))
      (node (ref "R24") (pin "1") (pinfunction "1_1") (pintype "passive"))
      (node (ref "R29") (pin "1") (pinfunction "1_1") (pintype "passive"))
      (node (ref "R7") (pin "1") (pinfunction "1_1") (pintype "passive"))
      (node (ref "R8") (pin "1") (pinfunction "1_1") (pintype "passive"))
      (node (ref "U$1") (pin "P$16") (pinfunction "P16_P$16") (pintype "bidirectional"))
      (node (ref "U$1") (pin "P$19") (pinfunction "P19_P$19") (pintype "bidirectional"))
      (node (ref "U$1") (pin "P$5") (pinfunction "P5_P$5") (pintype "bidirectional"))
      (node (ref "U$2") (pin "GND") (pinfunction "GND_GND") (pintype "bidirectional"))
      (node (ref "U$2") (pin "GND3") (pinfunction "GND3_GND3") (pintype "bidirectional"))
      (node (ref "U1") (pin "7") (pinfunction "GND_7") (pintype "bidirectional"))
      (node (ref "U2") (pin "7") (pinfunction "GND_7") (pintype "bidirectional"))
      (node (ref "U2") (pin "PAD") (pinfunction "GND_PAD") (pintype "bidirectional"))
      (node (ref "U2") (pin "PAD1") (pinfunction "GND_PAD1") (pintype "bidirectional"))
      (node (ref "U3") (pin "2") (pinfunction "VSS_2") (pintype "power_in"))
      (node (ref "U3") (pin "8") (pinfunction "STBY_8") (pintype "input"))
      (node (ref "U4") (pin "2") (pinfunction "VSS_2") (pintype "power_in"))
      (node (ref "U4") (pin "8") (pinfunction "STBY_8") (pintype "input"))
    )
    (net (code "48") (name "Net-(C10-Pad1)") (class "Default")
      (node (ref "C10") (pin "1") (pinfunction "1_1") (pintype "passive"))
      (node (ref "R10") (pin "1") (pinfunction "1_1") (pintype "passive"))
    )
    (net (code "49") (name "Net-(D6-CATHODE)") (class "Default")
      (node (ref "C18") (pin "2") (pinfunction "2_2") (pintype "passive"))
      (node (ref "D6") (pin "2") (pinfunction "CATHODE_2") (pintype "bidirectional"))
      (node (ref "L3") (pin "P$1") (pinfunction "P$1_P$1") (pintype "bidirectional"))
      (node (ref "U2") (pin "8") (pinfunction "SW_8") (pintype "bidirectional"))
    )
    (net (code "50") (name "Net-(H2-Pad6)") (class "Default")
      (node (ref "H2") (pin "6") (pinfunction "6_6") (pintype "bidirectional"))
      (node (ref "JP2") (pin "1") (pinfunction "1_1") (pintype "passive"))
    )
    (net (code "51") (name "Net-(H3-Pad1)") (class "Default")
      (node (ref "H3") (pin "1") (pinfunction "1_1") (pintype "bidirectional"))
      (node (ref "JP1") (pin "1") (pinfunction "1_1") (pintype "passive"))
    )
    (net (code "52") (name "Net-(H3-Pad2)") (class "Default")
      (node (ref "H3") (pin "2") (pinfunction "2_2") (pintype "bidirectional"))
      (node (ref "JP1") (pin "2") (pinfunction "2_2") (pintype "passive"))
    )
    (net (code "53") (name "Net-(H3-Pad3)") (class "Default")
      (node (ref "H3") (pin "3") (pinfunction "3_3") (pintype "bidirectional"))
      (node (ref "JP1") (pin "3") (pinfunction "3_3") (pintype "passive"))
    )
    (net (code "54") (name "Net-(H3-Pad4)") (class "Default")
      (node (ref "H3") (pin "4") (pinfunction "4_4") (pintype "bidirectional"))
      (node (ref "JP1") (pin "4") (pinfunction "4_4") (pintype "passive"))
    )
    (net (code "55") (name "Net-(H3-Pad5)") (class "Default")
      (node (ref "H3") (pin "5") (pinfunction "5_5") (pintype "bidirectional"))
      (node (ref "JP1") (pin "5") (pinfunction "5_5") (pintype "passive"))
    )
    (net (code "56") (name "Net-(H3-Pad6)") (class "Default")
      (node (ref "H3") (pin "6") (pinfunction "6_6") (pintype "bidirectional"))
      (node (ref "JP1") (pin "6") (pinfunction "6_6") (pintype "passive"))
    )
    (net (code "57") (name "Net-(H3-Pad7)") (class "Default")
      (node (ref "H3") (pin "7") (pinfunction "7_7") (pintype "bidirectional"))
      (node (ref "JP1") (pin "7") (pinfunction "7_7") (pintype "passive"))
    )
    (net (code "58") (name "Net-(H3-Pad8)") (class "Default")
      (node (ref "H3") (pin "8") (pinfunction "8_8") (pintype "bidirectional"))
      (node (ref "JP1") (pin "8") (pinfunction "8_8") (pintype "passive"))
    )
    (net (code "59") (name "Net-(J1-Pad1)") (class "Default")
      (node (ref "J1") (pin "1") (pinfunction "1_1") (pintype "bidirectional"))
      (node (ref "R2") (pin "2") (pinfunction "2_2") (pintype "passive"))
    )
    (net (code "60") (name "Net-(J1-Pad2)") (class "Default")
      (node (ref "J1") (pin "2") (pinfunction "2_2") (pintype "bidirectional"))
      (node (ref "R1") (pin "2") (pinfunction "2_2") (pintype "passive"))
    )
    (net (code "61") (name "Net-(LED1-DI)") (class "Default")
      (node (ref "LED1") (pin "4-DIN") (pinfunction "DI_4-DIN") (pintype "input"))
      (node (ref "R12") (pin "1") (pinfunction "1_1") (pintype "passive"))
      (node (ref "R9") (pin "1") (pinfunction "1_1") (pintype "passive"))
    )
    (net (code "62") (name "Net-(LED1-DO)") (class "Default")
      (node (ref "LED1") (pin "2-DOUT") (pinfunction "DO_2-DOUT") (pintype "output"))
      (node (ref "LED2") (pin "4-DIN") (pinfunction "DI_4-DIN") (pintype "input"))
      (node (ref "R12") (pin "2") (pinfunction "2_2") (pintype "passive"))
    )
    (net (code "63") (name "Net-(LED2-DO)") (class "Default")
      (node (ref "LED2") (pin "2-DOUT") (pinfunction "DO_2-DOUT") (pintype "output"))
      (node (ref "LED3") (pin "4-DIN") (pinfunction "DI_4-DIN") (pintype "input"))
    )
    (net (code "64") (name "Net-(LED3-DO)") (class "Default")
      (node (ref "LED3") (pin "2-DOUT") (pinfunction "DO_2-DOUT") (pintype "output"))
      (node (ref "LED4") (pin "4-DIN") (pinfunction "DI_4-DIN") (pintype "input"))
    )
    (net (code "65") (name "Net-(LED4-DO)") (class "Default")
      (node (ref "LED4") (pin "2-DOUT") (pinfunction "DO_2-DOUT") (pintype "output"))
      (node (ref "LED5") (pin "4-DIN") (pinfunction "DI_4-DIN") (pintype "input"))
    )
    (net (code "66") (name "Net-(LED5-DO)") (class "Default")
      (node (ref "LED5") (pin "2-DOUT") (pinfunction "DO_2-DOUT") (pintype "output"))
      (node (ref "LED6") (pin "4-DIN") (pinfunction "DI_4-DIN") (pintype "input"))
    )
    (net (code "67") (name "Net-(LED6-DO)") (class "Default")
      (node (ref "LED6") (pin "2-DOUT") (pinfunction "DO_2-DOUT") (pintype "output"))
      (node (ref "LED7") (pin "4-DIN") (pinfunction "DI_4-DIN") (pintype "input"))
    )
    (net (code "68") (name "Net-(LED7-DO)") (class "Default")
      (node (ref "LED7") (pin "2-DOUT") (pinfunction "DO_2-DOUT") (pintype "output"))
      (node (ref "LED8") (pin "4-DIN") (pinfunction "DI_4-DIN") (pintype "input"))
    )
    (net (code "69") (name "Net-(LED8-DO)") (class "Default")
      (node (ref "LED8") (pin "2-DOUT") (pinfunction "DO_2-DOUT") (pintype "output"))
      (node (ref "LED9") (pin "4-DIN") (pinfunction "DI_4-DIN") (pintype "input"))
    )
    (net (code "70") (name "Net-(LED10-DI)") (class "Default")
      (node (ref "LED10") (pin "4-DIN") (pinfunction "DI_4-DIN") (pintype "input"))
      (node (ref "LED9") (pin "2-DOUT") (pinfunction "DO_2-DOUT") (pintype "output"))
    )
    (net (code "71") (name "Net-(LED10-DO)") (class "Default")
      (node (ref "LED10") (pin "2-DOUT") (pinfunction "DO_2-DOUT") (pintype "output"))
      (node (ref "LED11") (pin "4-DIN") (pinfunction "DI_4-DIN") (pintype "input"))
    )
    (net (code "72") (name "Net-(LED11-DO)") (class "Default")
      (node (ref "LED11") (pin "2-DOUT") (pinfunction "DO_2-DOUT") (pintype "output"))
      (node (ref "LED12") (pin "4-DIN") (pinfunction "DI_4-DIN") (pintype "input"))
    )
    (net (code "73") (name "Net-(LED13-PadC)") (class "Default")
      (node (ref "LED13") (pin "C") (pinfunction "C_C") (pintype "passive"))
      (node (ref "R13") (pin "2") (pinfunction "2_2") (pintype "passive"))
    )
    (net (code "74") (name "Net-(LED14-PadC)") (class "Default")
      (node (ref "LED14") (pin "C") (pinfunction "C_C") (pintype "passive"))
      (node (ref "R14") (pin "2") (pinfunction "2_2") (pintype "passive"))
    )
    (net (code "75") (name "Net-(LED15-PadC)") (class "Default")
      (node (ref "LED15") (pin "C") (pinfunction "C_C") (pintype "passive"))
      (node (ref "R15") (pin "2") (pinfunction "2_2") (pintype "passive"))
    )
    (net (code "76") (name "Net-(U1-A2)") (class "Default")
      (node (ref "U$2") (pin "21/A7") (pinfunction "21/A7_21/A7") (pintype "bidirectional"))
      (node (ref "U1") (pin "3") (pinfunction "A2_3") (pintype "bidirectional"))
    )
    (net (code "77") (name "Net-(U1-Y1)") (class "Default")
      (node (ref "JP5") (pin "1") (pinfunction "1_1") (pintype "passive"))
      (node (ref "R9") (pin "2") (pinfunction "2_2") (pintype "passive"))
      (node (ref "U1") (pin "13") (pinfunction "Y1_13") (pintype "bidirectional"))
    )
    (net (code "78") (name "Net-(U1-Y2)") (class "Default")
      (node (ref "JP5") (pin "2") (pinfunction "2_2") (pintype "passive"))
      (node (ref "R11") (pin "2") (pinfunction "2_2") (pintype "passive"))
      (node (ref "U1") (pin "12") (pinfunction "Y2_12") (pintype "bidirectional"))
    )
    (net (code "79") (name "Net-(U2-BOOT)") (class "Default")
      (node (ref "C18") (pin "1") (pinfunction "1_1") (pintype "passive"))
      (node (ref "U2") (pin "1") (pinfunction "BOOT_1") (pintype "bidirectional"))
    )
    (net (code "80") (name "Net-(U2-COMP)") (class "Default")
      (node (ref "C12") (pin "1") (pinfunction "1_1") (pintype "passive"))
      (node (ref "R10") (pin "2") (pinfunction "2_2") (pintype "passive"))
      (node (ref "U2") (pin "6") (pinfunction "COMP_6") (pintype "bidirectional"))
    )
    (net (code "81") (name "Net-(U2-EN)") (class "Default")
      (node (ref "R6") (pin "1") (pinfunction "1_1") (pintype "passive"))
      (node (ref "R7") (pin "2") (pinfunction "2_2") (pintype "passive"))
      (node (ref "U2") (pin "3") (pinfunction "EN_3") (pintype "bidirectional"))
    )
    (net (code "82") (name "Net-(U2-FB)") (class "Default")
      (node (ref "R28") (pin "1") (pinfunction "1_1") (pintype "passive"))
      (node (ref "R29") (pin "2") (pinfunction "2_2") (pintype "passive"))
      (node (ref "U2") (pin "5") (pinfunction "FB_5") (pintype "bidirectional"))
    )
    (net (code "83") (name "Net-(U2-RT{slash}CLK)") (class "Default")
      (node (ref "R8") (pin "2") (pinfunction "2_2") (pintype "passive"))
      (node (ref "U2") (pin "4") (pinfunction "RT/CLK_4") (pintype "bidirectional"))
    )
    (net (code "84") (name "unconnected-(LED12-DO-Pad2-DOUT)") (class "Default")
      (node (ref "LED12") (pin "2-DOUT") (pinfunction "DO_2-DOUT") (pintype "output"))
    )
    (net (code "85") (name "unconnected-(U$2-A21{slash}DAC0-Pad21{slash}DAC0)") (class "Default")
      (node (ref "U$2") (pin "21/DAC0") (pinfunction "A21/DAC0_21/DAC0") (pintype "bidirectional"))
    )
    (net (code "86") (name "unconnected-(U$2-Pad0{slash}RX)") (class "Default")
      (node (ref "U$2") (pin "0/RX") (pinfunction "0/RX_0/RX") (pintype "bidirectional"))
    )
    (net (code "87") (name "unconnected-(U$2-Pad1{slash}TX)") (class "Default")
      (node (ref "U$2") (pin "1/TX") (pinfunction "1/TX_1/TX") (pintype "bidirectional"))
    )
    (net (code "88") (name "unconnected-(U$2-Pad3V3_2)") (class "Default")
      (node (ref "U$2") (pin "3V3_2") (pinfunction "3V3_2_3V3_2") (pintype "bidirectional"))
    )
    (net (code "89") (name "unconnected-(U$2-Pad3V3_LO)") (class "Default")
      (node (ref "U$2") (pin "3V3_LO") (pinfunction "3V3_LO_3V3_LO") (pintype "bidirectional"))
    )
    (net (code "90") (name "unconnected-(U$2-Pad18{slash}A4{slash}SDA)") (class "Default")
      (node (ref "U$2") (pin "18/A4/SDA") (pinfunction "18/A4/SDA_18/A4/SDA") (pintype "bidirectional"))
    )
    (net (code "91") (name "unconnected-(U$2-Pad19{slash}A5{slash}SCL)") (class "Default")
      (node (ref "U$2") (pin "19/A5/SCL") (pinfunction "19/A5/SCL_19/A5/SCL") (pintype "bidirectional"))
    )
    (net (code "92") (name "unconnected-(U$2-Pad23{slash}A9)") (class "Default")
      (node (ref "U$2") (pin "23/A9") (pinfunction "23/A9_23/A9") (pintype "bidirectional"))
    )
    (net (code "93") (name "unconnected-(U$2-Pad29)") (class "Default")
      (node (ref "U$2") (pin "29") (pinfunction "29_29") (pintype "bidirectional"))
    )
    (net (code "94") (name "unconnected-(U$2-Pad30)") (class "Default")
      (node (ref "U$2") (pin "30") (pinfunction "30_30") (pintype "bidirectional"))
    )
    (net (code "95") (name "unconnected-(U$2-Pad31{slash}A12)") (class "Default")
      (node (ref "U$2") (pin "31/A12") (pinfunction "31/A12_31/A12") (pintype "bidirectional"))
    )
    (net (code "96") (name "unconnected-(U$2-PadA10)") (class "Default")
      (node (ref "U$2") (pin "A10") (pinfunction "A10_A10") (pintype "bidirectional"))
    )
    (net (code "97") (name "unconnected-(U$2-PadA11)") (class "Default")
      (node (ref "U$2") (pin "A11") (pinfunction "A11_A11") (pintype "bidirectional"))
    )
    (net (code "98") (name "unconnected-(U$2-PadA22{slash}DAC1)") (class "Default")
      (node (ref "U$2") (pin "A22/DAC1") (pinfunction "A22/DAC1_A22/DAC1") (pintype "bidirectional"))
    )
    (net (code "99") (name "unconnected-(U$2-PadAGND)") (class "Default")
      (node (ref "U$2") (pin "AGND") (pinfunction "AGND_AGND") (pintype "bidirectional"))
    )
    (net (code "100") (name "unconnected-(U$2-PadAREF)") (class "Default")
      (node (ref "U$2") (pin "AREF") (pinfunction "AREF_AREF") (pintype "bidirectional"))
    )
    (net (code "101") (name "unconnected-(U$2-PadGND2)") (class "Default")
      (node (ref "U$2") (pin "GND2") (pinfunction "GND2_GND2") (pintype "bidirectional"))
    )
    (net (code "102") (name "unconnected-(U$2-PadPROG)") (class "Default")
      (node (ref "U$2") (pin "PROG") (pinfunction "PROG_PROG") (pintype "bidirectional"))
    )
    (net (code "103") (name "unconnected-(U$2-PadRESET)") (class "Default")
      (node (ref "U$2") (pin "RESET") (pinfunction "RESET_RESET") (pintype "bidirectional"))
    )
    (net (code "104") (name "unconnected-(U$2-PadU5V)") (class "Default")
      (node (ref "U$2") (pin "U5V") (pinfunction "U5V_U5V") (pintype "bidirectional"))
    )
    (net (code "105") (name "unconnected-(U$2-PadUD+)") (class "Default")
      (node (ref "U$2") (pin "UD+") (pinfunction "UD+_UD+") (pintype "bidirectional"))
    )
    (net (code "106") (name "unconnected-(U$2-PadUD-)") (class "Default")
      (node (ref "U$2") (pin "UD-") (pinfunction "UD-_UD-") (pintype "bidirectional"))
    )
    (net (code "107") (name "unconnected-(U$2-PadUGND1)") (class "Default")
      (node (ref "U$2") (pin "UGND1") (pinfunction "UGND1_UGND1") (pintype "bidirectional"))
    )
    (net (code "108") (name "unconnected-(U$2-PadUGND2)") (class "Default")
      (node (ref "U$2") (pin "UGND2") (pinfunction "UGND2_UGND2") (pintype "bidirectional"))
    )
    (net (code "109") (name "unconnected-(U$2-PadVBAT)") (class "Default")
      (node (ref "U$2") (pin "VBAT") (pinfunction "VBAT_VBAT") (pintype "bidirectional"))
    )
    (net (code "110") (name "unconnected-(U$2-PadVUSB)") (class "Default")
      (node (ref "U$2") (pin "VUSB") (pinfunction "VUSB_VUSB") (pintype "bidirectional"))
    )
    (net (code "111") (name "unconnected-(U1-A3-Pad4)") (class "Default")
      (node (ref "U1") (pin "4") (pinfunction "A3_4") (pintype "bidirectional"))
    )
    (net (code "112") (name "unconnected-(U1-A4-Pad5)") (class "Default")
      (node (ref "U1") (pin "5") (pinfunction "A4_5") (pintype "bidirectional"))
    )
    (net (code "113") (name "unconnected-(U1-Y3-Pad11)") (class "Default")
      (node (ref "U1") (pin "11") (pinfunction "Y3_11") (pintype "bidirectional"))
    )
    (net (code "114") (name "unconnected-(U1-Y4-Pad10)") (class "Default")
      (node (ref "U1") (pin "10") (pinfunction "Y4_10") (pintype "bidirectional"))
    )
  )
)
